# Power.net
KiCad netlist of a schematic drawn in Altium Designer
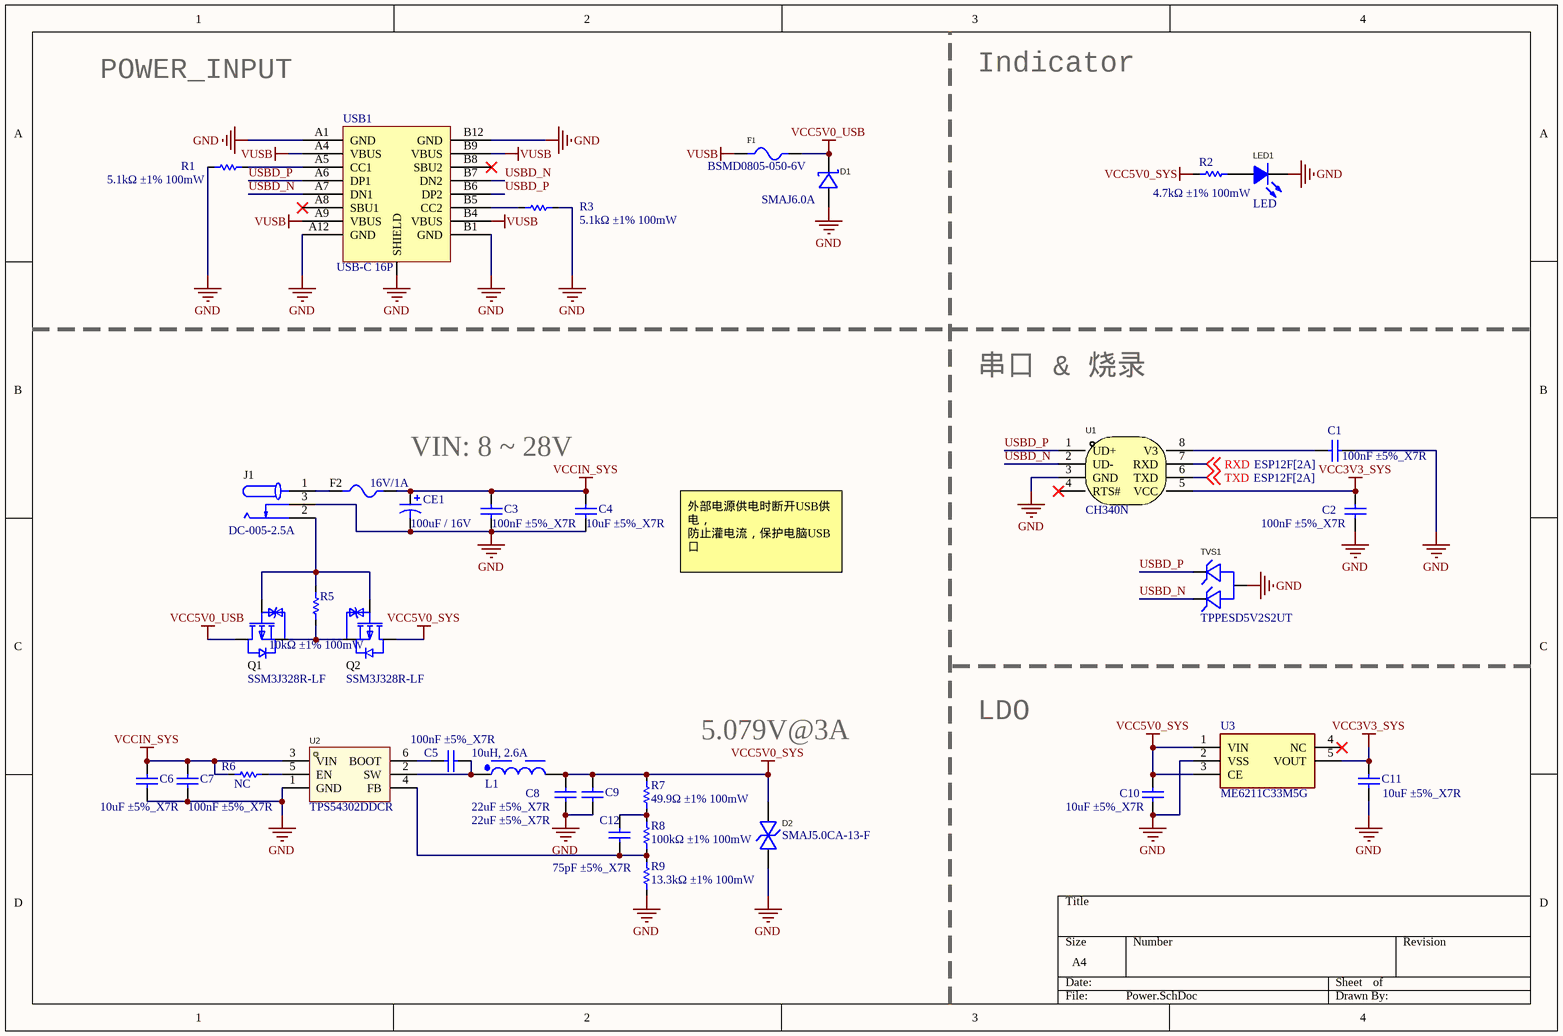
[diagram p0: Power.SchDoc]

(export (version "E")
  (design (tool "Eeschema 10.0.6"))
  (components
    (comp (ref "C1")
      (value "100nF ±5%_X7R")
      (footprint "C0603")
      (description "Capacitor")
      (fields (field (name "PUBLISHER") "Altium Limited"))
      (libsource (lib "Component") (part "Cap"))
    )
    (comp (ref "C2")
      (value "100nF ±5%_X7R")
      (footprint "C0603")
      (description "Capacitor")
      (fields (field (name "PUBLISHER") "Altium Limited"))
      (libsource (lib "Component") (part "Cap"))
    )
    (comp (ref "C3")
      (value "100nF ±5%_X7R")
      (footprint "C0603")
      (description "Capacitor")
      (fields (field (name "PUBLISHER") "Altium Limited"))
      (libsource (lib "Component") (part "Cap"))
    )
    (comp (ref "C4")
      (value "10uF ±5%_X7R")
      (footprint "C0603")
      (description "Capacitor")
      (fields (field (name "PUBLISHER") "Altium Limited"))
      (libsource (lib "Component") (part "Cap"))
    )
    (comp (ref "C5")
      (value "100nF ±5%_X7R")
      (footprint "C0402")
      (description "Capacitor")
      (fields (field (name "PUBLISHER") "Altium Limited"))
      (libsource (lib "Component") (part "Cap"))
    )
    (comp (ref "C6")
      (value "10uF ±5%_X7R")
      (footprint "C0603")
      (description "Capacitor")
      (fields (field (name "PUBLISHER") "Altium Limited"))
      (libsource (lib "Component") (part "Cap"))
    )
    (comp (ref "C7")
      (value "100nF ±5%_X7R")
      (footprint "C0603")
      (description "Capacitor")
      (fields (field (name "PUBLISHER") "Altium Limited"))
      (libsource (lib "Component") (part "Cap"))
    )
    (comp (ref "C8")
      (value "22uF ±5%_X7R")
      (footprint "C0603")
      (description "Capacitor")
      (fields (field (name "PUBLISHER") "Altium Limited"))
      (libsource (lib "Component") (part "Cap"))
    )
    (comp (ref "C9")
      (value "22uF ±5%_X7R")
      (footprint "C0603")
      (description "Capacitor")
      (fields (field (name "PUBLISHER") "Altium Limited"))
      (libsource (lib "Component") (part "Cap"))
    )
    (comp (ref "C10")
      (value "10uF ±5%_X7R")
      (footprint "C0603")
      (description "Capacitor")
      (fields (field (name "PUBLISHER") "Altium Limited"))
      (libsource (lib "Component") (part "Cap"))
    )
    (comp (ref "C11")
      (value "10uF ±5%_X7R")
      (footprint "C0603")
      (description "Capacitor")
      (fields (field (name "PUBLISHER") "Altium Limited"))
      (libsource (lib "Component") (part "Cap"))
    )
    (comp (ref "C12")
      (value "75pF ±5%_X7R")
      (footprint "C0402")
      (description "Capacitor")
      (fields (field (name "PUBLISHER") "Altium Limited"))
      (libsource (lib "Component") (part "Cap"))
    )
    (comp (ref "CE1")
      (value "100uF / 16V")
      (footprint "CAP-SMD")
      (description "Polarized Capacitor (Axial)")
      (fields (field (name "PUBLISHER") "Altium Limited"))
      (libsource (lib "Component") (part "Cap Pol"))
    )
    (comp (ref "D1")
      (value "SMAJ6.0A")
      (footprint "SMA_L4.4-W2.6-LS5.0-RD")
      (fields (field (name "MANUFACTURER") "BORN(伯恩半导体)"))
      (libsource (lib "Component") (part "SMAJ6.0A_C152112"))
    )
    (comp (ref "D2")
      (value "SMAJ5.0CA-13-F")
      (footprint "SMA_L4.4-W2.6-LS5.0-BI")
      (fields (field (name "MANUFACTURER") "DIODES(美台)"))
      (libsource (lib "Component") (part "SMAJ5.0CA"))
    )
    (comp (ref "F1")
      (value "BSMD0805-050-6V")
      (footprint "F0805")
      (fields (field (name "MANUFACTURER") "BHFUSE(佰宏)"))
      (libsource (lib "Component_Footprints") (part "BSMD0805-050-6V"))
    )
    (comp (ref "F2")
      (value "16V/1A")
      (footprint "F1206")
      (fields (field (name "MANUFACTURER") "BHFUSE(佰宏)") (field (name "MANUFACTURER PART") "BSMD0805-050-6V"))
      (libsource (lib "Component") (part "FUSE"))
    )
    (comp (ref "J1")
      (value "DC-005-2.5A")
      (footprint "CONN-TH_DC-005-2.5A-2.0")
      (fields
        (field (name "MANUFACTURER") "XKB Connectivity(中国星坤)")
        (field (name "MANUFACTURER PART") "DC-005-2.5A-2.5")
      )
      (libsource (lib "Connectivity_Plugs") (part "DC-005"))
    )
    (comp (ref "L1")
      (value "10uH, 2.6A")
      (footprint "WE-PD_7345P")
      (description "WE-PD SMT Power Inductor, size 7345P, 10uH, 2.6A, 45mOhm")
      (fields
        (field (name "MANUFACTURER PART NUMBER") "7447773100")
        (field (name "MANUFACTURER") "Wurth Elektronik")
      )
      (libsource (lib "WE-PD (rev22g)") (part "7447773100"))
    )
    (comp (ref "LED1")
      (value "LED")
      (footprint "LED0603-RD")
      (fields
        (field (name "MANUFACTURER") "EVERLIGHT(亿光)")
        (field (name "MANUFACTURER PART") "17-21SURC/S530-A2/TR8")
      )
      (libsource (lib "Component") (part "LED"))
    )
    (comp (ref "Q1")
      (value "SSM3J328R-LF")
      (footprint "SOT-23-3_L2.9-W1.4-P1.91-LS2.6-BR")
      (fields (field (name "MANUFACTURER") "VBsemi(微碧)") (field (name "MANUFACTURER PART") "SSM3J328R-VB"))
      (libsource (lib "Component") (part "MOSFET"))
    )
    (comp (ref "Q2")
      (value "SSM3J328R-LF")
      (footprint "SOT-23-3_L2.9-W1.4-P1.91-LS2.6-BR")
      (fields (field (name "MANUFACTURER") "VBsemi(微碧)") (field (name "MANUFACTURER PART") "SSM3J328R-VB"))
      (libsource (lib "Component") (part "MOSFET"))
    )
    (comp (ref "R1")
      (value "5.1kΩ ±1% 100mW")
      (footprint "R0402")
      (description "Resistor")
      (fields (field (name "PUBLISHER") "Altium Limited"))
      (libsource (lib "Component_Footprints") (part "Res"))
    )
    (comp (ref "R2")
      (value "4.7kΩ ±1% 100mW")
      (footprint "R0603")
      (description "Resistor")
      (fields (field (name "PUBLISHER") "Altium Limited"))
      (libsource (lib "Component_Footprints") (part "Res"))
    )
    (comp (ref "R3")
      (value "5.1kΩ ±1% 100mW")
      (footprint "R0402")
      (description "Resistor")
      (fields (field (name "PUBLISHER") "Altium Limited"))
      (libsource (lib "Component_Footprints") (part "Res"))
    )
    (comp (ref "R5")
      (value "10kΩ ±1% 100mW")
      (footprint "R0603")
      (description "Resistor")
      (fields (field (name "PUBLISHER") "Altium Limited"))
      (libsource (lib "Component") (part "Res"))
    )
    (comp (ref "R6")
      (value "NC")
      (footprint "R0402")
      (description "Resistor")
      (fields (field (name "PUBLISHER") "Altium Limited"))
      (libsource (lib "Component") (part "Res"))
    )
    (comp (ref "R7")
      (value "49.9Ω ±1% 100mW")
      (footprint "R0402")
      (description "Resistor")
      (fields (field (name "PUBLISHER") "Altium Limited"))
      (libsource (lib "Component") (part "Res"))
    )
    (comp (ref "R8")
      (value "100kΩ ±1% 100mW")
      (footprint "R0402")
      (description "Resistor")
      (fields (field (name "PUBLISHER") "Altium Limited"))
      (libsource (lib "Component") (part "Res"))
    )
    (comp (ref "R9")
      (value "13.3kΩ ±1% 100mW")
      (footprint "R0402")
      (description "Resistor")
      (fields (field (name "PUBLISHER") "Altium Limited"))
      (libsource (lib "Component") (part "Res"))
    )
    (comp (ref "TVS1")
      (value "TPPESD5V2S2UT")
      (footprint "SOT-23-3_L2.9-W1.3-P1.90-LS2.4-BR")
      (fields (field (name "MANUFACTURER") "TECH PUBLIC(台舟)"))
      (libsource (lib "Component") (part "TVS"))
    )
    (comp (ref "U1")
      (value "CH340N")
      (footprint "SOP-8_L4.9-W3.9-P1.27-LS6.0-BL")
      (fields (field (name "MANUFACTURER") "WCH(南京沁恒)"))
      (libsource (lib "IC") (part "CH340N"))
    )
    (comp (ref "U2")
      (value "TPS54302DDCR")
      (footprint "SOT-23-6_L2.9-W1.6-P0.95-LS2.8-BL")
      (fields (field (name "MANUFACTURER") "TI(德州仪器)"))
      (libsource (lib "IC") (part "TPS54302DDCR"))
    )
    (comp (ref "U3")
      (value "ME6211C33M5G")
      (footprint "SamacSys:SOT95P282X145-5N")
      (description "Integrated Circuit")
      (libsource (lib "*") (part "ME6211C33M5G"))
    )
    (comp (ref "USB1") (value "USB-C 16P") (footprint "USB-C-16P") (libsource (lib "USB") (part "USB-C 16P")))
  )
  (nets
    (net (code "1") (name "/USBD_N") (class "Default")
      (node (ref "TVS1") (pin "1") (pinfunction "A_1") (pintype "passive"))
      (node (ref "U1") (pin "2") (pinfunction "UD-_2") (pintype "passive"))
      (node (ref "USB1") (pin "A7") (pinfunction "DN1_A7") (pintype "passive"))
      (node (ref "USB1") (pin "B7") (pinfunction "DN2_B7") (pintype "passive"))
    )
    (net (code "2") (name "/USBD_P") (class "Default")
      (node (ref "TVS1") (pin "2") (pinfunction "A_2") (pintype "passive"))
      (node (ref "U1") (pin "1") (pinfunction "UD+_1") (pintype "passive"))
      (node (ref "USB1") (pin "A6") (pinfunction "DP1_A6") (pintype "passive"))
      (node (ref "USB1") (pin "B6") (pinfunction "DP2_B6") (pintype "passive"))
    )
    (net (code "3") (name "GND") (class "Default")
      (node (ref "C1") (pin "1") (pinfunction "1_1") (pintype "passive"))
      (node (ref "C10") (pin "1") (pinfunction "1_1") (pintype "passive"))
      (node (ref "C11") (pin "1") (pinfunction "1_1") (pintype "passive"))
      (node (ref "C2") (pin "1") (pinfunction "1_1") (pintype "passive"))
      (node (ref "C3") (pin "1") (pinfunction "1_1") (pintype "passive"))
      (node (ref "C4") (pin "1") (pinfunction "1_1") (pintype "passive"))
      (node (ref "C6") (pin "1") (pinfunction "1_1") (pintype "passive"))
      (node (ref "C7") (pin "1") (pinfunction "1_1") (pintype "passive"))
      (node (ref "C8") (pin "1") (pinfunction "1_1") (pintype "passive"))
      (node (ref "C9") (pin "1") (pinfunction "1_1") (pintype "passive"))
      (node (ref "CE1") (pin "2") (pinfunction "2_2") (pintype "passive"))
      (node (ref "D1") (pin "2") (pinfunction "A_2") (pintype "passive"))
      (node (ref "D2") (pin "1") (pinfunction "1_1") (pintype "passive"))
      (node (ref "J1") (pin "3") (pinfunction "3_3") (pintype "passive"))
      (node (ref "LED1") (pin "2") (pinfunction "K_2") (pintype "passive"))
      (node (ref "R1") (pin "1") (pinfunction "1_1") (pintype "passive"))
      (node (ref "R3") (pin "2") (pinfunction "2_2") (pintype "passive"))
      (node (ref "R9") (pin "1") (pinfunction "1_1") (pintype "passive"))
      (node (ref "TVS1") (pin "3") (pinfunction "K_3") (pintype "passive"))
      (node (ref "U1") (pin "3") (pinfunction "GND_3") (pintype "passive"))
      (node (ref "U2") (pin "1") (pinfunction "GND_1") (pintype "passive"))
      (node (ref "U3") (pin "2") (pinfunction "VSS_2") (pintype "passive"))
      (node (ref "USB1") (pin "0") (pinfunction "SHIELD_0") (pintype "passive"))
      (node (ref "USB1") (pin "A1") (pinfunction "GND_A1") (pintype "passive"))
      (node (ref "USB1") (pin "A12") (pinfunction "GND_A12") (pintype "passive"))
      (node (ref "USB1") (pin "B1") (pinfunction "GND_B1") (pintype "passive"))
      (node (ref "USB1") (pin "B12") (pinfunction "GND_B12") (pintype "passive"))
    )
    (net (code "4") (name "Net-(C12-Pad2)") (class "Default")
      (node (ref "C12") (pin "2") (pinfunction "2_2") (pintype "passive"))
      (node (ref "R7") (pin "1") (pinfunction "1_1") (pintype "passive"))
      (node (ref "R8") (pin "2") (pinfunction "2_2") (pintype "passive"))
    )
    (net (code "5") (name "Net-(F2-Pad1)") (class "Default")
      (node (ref "F2") (pin "1") (pinfunction "1_1") (pintype "passive"))
      (node (ref "J1") (pin "1") (pinfunction "1_1") (pintype "passive"))
    )
    (net (code "6") (name "Net-(LED1-A)") (class "Default")
      (node (ref "LED1") (pin "1") (pinfunction "A_1") (pintype "passive"))
      (node (ref "R2") (pin "2") (pinfunction "2_2") (pintype "passive"))
    )
    (net (code "7") (name "Net-(Q1-G)") (class "Default")
      (node (ref "J1") (pin "2") (pinfunction "2_2") (pintype "passive"))
      (node (ref "Q1") (pin "1") (pinfunction "G_1") (pintype "passive"))
      (node (ref "Q2") (pin "1") (pinfunction "G_1") (pintype "passive"))
      (node (ref "R5") (pin "1") (pinfunction "1_1") (pintype "passive"))
    )
    (net (code "8") (name "Net-(Q1-S)") (class "Default")
      (node (ref "Q1") (pin "2") (pinfunction "S_2") (pintype "passive"))
      (node (ref "Q2") (pin "2") (pinfunction "S_2") (pintype "passive"))
      (node (ref "R5") (pin "2") (pinfunction "2_2") (pintype "passive"))
    )
    (net (code "9") (name "Net-(U1-V3)") (class "Default")
      (node (ref "C1") (pin "2") (pinfunction "2_2") (pintype "passive"))
      (node (ref "U1") (pin "8") (pinfunction "V3_8") (pintype "passive"))
    )
    (net (code "10") (name "Net-(U2-BOOT)") (class "Default")
      (node (ref "C5") (pin "2") (pinfunction "2_2") (pintype "passive"))
      (node (ref "U2") (pin "6") (pinfunction "BOOT_6") (pintype "passive"))
    )
    (net (code "11") (name "Net-(U2-EN)") (class "Default")
      (node (ref "R6") (pin "1") (pinfunction "1_1") (pintype "passive"))
      (node (ref "U2") (pin "5") (pinfunction "EN_5") (pintype "passive"))
    )
    (net (code "12") (name "Net-(U2-FB)") (class "Default")
      (node (ref "C12") (pin "1") (pinfunction "1_1") (pintype "passive"))
      (node (ref "R8") (pin "1") (pinfunction "1_1") (pintype "passive"))
      (node (ref "R9") (pin "2") (pinfunction "2_2") (pintype "passive"))
      (node (ref "U2") (pin "4") (pinfunction "FB_4") (pintype "passive"))
    )
    (net (code "13") (name "Net-(U2-SW)") (class "Default")
      (node (ref "C5") (pin "1") (pinfunction "1_1") (pintype "passive"))
      (node (ref "L1") (pin "1") (pinfunction "1_1") (pintype "passive"))
      (node (ref "U2") (pin "2") (pinfunction "SW_2") (pintype "passive"))
    )
    (net (code "14") (name "Net-(USB1-CC1)") (class "Default")
      (node (ref "R1") (pin "2") (pinfunction "2_2") (pintype "passive"))
      (node (ref "USB1") (pin "A5") (pinfunction "CC1_A5") (pintype "passive"))
    )
    (net (code "15") (name "Net-(USB1-CC2)") (class "Default")
      (node (ref "R3") (pin "1") (pinfunction "1_1") (pintype "passive"))
      (node (ref "USB1") (pin "B5") (pinfunction "CC2_B5") (pintype "passive"))
    )
    (net (code "16") (name "RXD") (class "Default")
      (node (ref "U1") (pin "7") (pinfunction "RXD_7") (pintype "passive"))
    )
    (net (code "17") (name "TXD") (class "Default")
      (node (ref "U1") (pin "6") (pinfunction "TXD_6") (pintype "passive"))
    )
    (net (code "18") (name "VCC3V3_SYS") (class "Default")
      (node (ref "C11") (pin "2") (pinfunction "2_2") (pintype "passive"))
      (node (ref "C2") (pin "2") (pinfunction "2_2") (pintype "passive"))
      (node (ref "U1") (pin "5") (pinfunction "VCC_5") (pintype "passive"))
      (node (ref "U3") (pin "5") (pinfunction "VOUT_5") (pintype "passive"))
    )
    (net (code "19") (name "VCC5V0_SYS") (class "Default")
      (node (ref "C10") (pin "2") (pinfunction "2_2") (pintype "passive"))
      (node (ref "C8") (pin "2") (pinfunction "2_2") (pintype "passive"))
      (node (ref "C9") (pin "2") (pinfunction "2_2") (pintype "passive"))
      (node (ref "D2") (pin "2") (pinfunction "2_2") (pintype "passive"))
      (node (ref "L1") (pin "2") (pinfunction "2_2") (pintype "passive"))
      (node (ref "Q2") (pin "3") (pinfunction "D_3") (pintype "passive"))
      (node (ref "R2") (pin "1") (pinfunction "1_1") (pintype "passive"))
      (node (ref "R7") (pin "2") (pinfunction "2_2") (pintype "passive"))
      (node (ref "U3") (pin "1") (pinfunction "VIN_1") (pintype "passive"))
      (node (ref "U3") (pin "3") (pinfunction "CE_3") (pintype "passive"))
    )
    (net (code "20") (name "VCC5V0_USB") (class "Default")
      (node (ref "D1") (pin "1") (pinfunction "K_1") (pintype "passive"))
      (node (ref "F1") (pin "2") (pinfunction "2_2") (pintype "passive"))
      (node (ref "Q1") (pin "3") (pinfunction "D_3") (pintype "passive"))
    )
    (net (code "21") (name "VCCIN_SYS") (class "Default")
      (node (ref "C3") (pin "2") (pinfunction "2_2") (pintype "passive"))
      (node (ref "C4") (pin "2") (pinfunction "2_2") (pintype "passive"))
      (node (ref "C6") (pin "2") (pinfunction "2_2") (pintype "passive"))
      (node (ref "C7") (pin "2") (pinfunction "2_2") (pintype "passive"))
      (node (ref "CE1") (pin "1") (pinfunction "1_1") (pintype "passive"))
      (node (ref "F2") (pin "2") (pinfunction "2_2") (pintype "passive"))
      (node (ref "R6") (pin "2") (pinfunction "2_2") (pintype "passive"))
      (node (ref "U2") (pin "3") (pinfunction "VIN_3") (pintype "passive"))
    )
    (net (code "22") (name "VUSB") (class "Default")
      (node (ref "F1") (pin "1") (pinfunction "1_1") (pintype "passive"))
      (node (ref "USB1") (pin "A4") (pinfunction "VBUS_A4") (pintype "passive"))
      (node (ref "USB1") (pin "A9") (pinfunction "VBUS_A9") (pintype "passive"))
      (node (ref "USB1") (pin "B4") (pinfunction "VBUS_B4") (pintype "passive"))
      (node (ref "USB1") (pin "B9") (pinfunction "VBUS_B9") (pintype "passive"))
    )
    (net (code "23") (name "unconnected-(U1-RTS#-Pad4)") (class "Default")
      (node (ref "U1") (pin "4") (pinfunction "RTS#_4") (pintype "passive+no_connect"))
    )
    (net (code "24") (name "unconnected-(U3-NC-Pad4)") (class "Default")
      (node (ref "U3") (pin "4") (pinfunction "NC_4") (pintype "passive+no_connect"))
    )
    (net (code "25") (name "unconnected-(USB1-SBU1-PadA8)") (class "Default")
      (node (ref "USB1") (pin "A8") (pinfunction "SBU1_A8") (pintype "passive+no_connect"))
    )
    (net (code "26") (name "unconnected-(USB1-SBU2-PadB8)") (class "Default")
      (node (ref "USB1") (pin "B8") (pinfunction "SBU2_B8") (pintype "passive+no_connect"))
    )
  )
)
